# board1.net
KiCad netlist of a schematic drawn in EAGLE
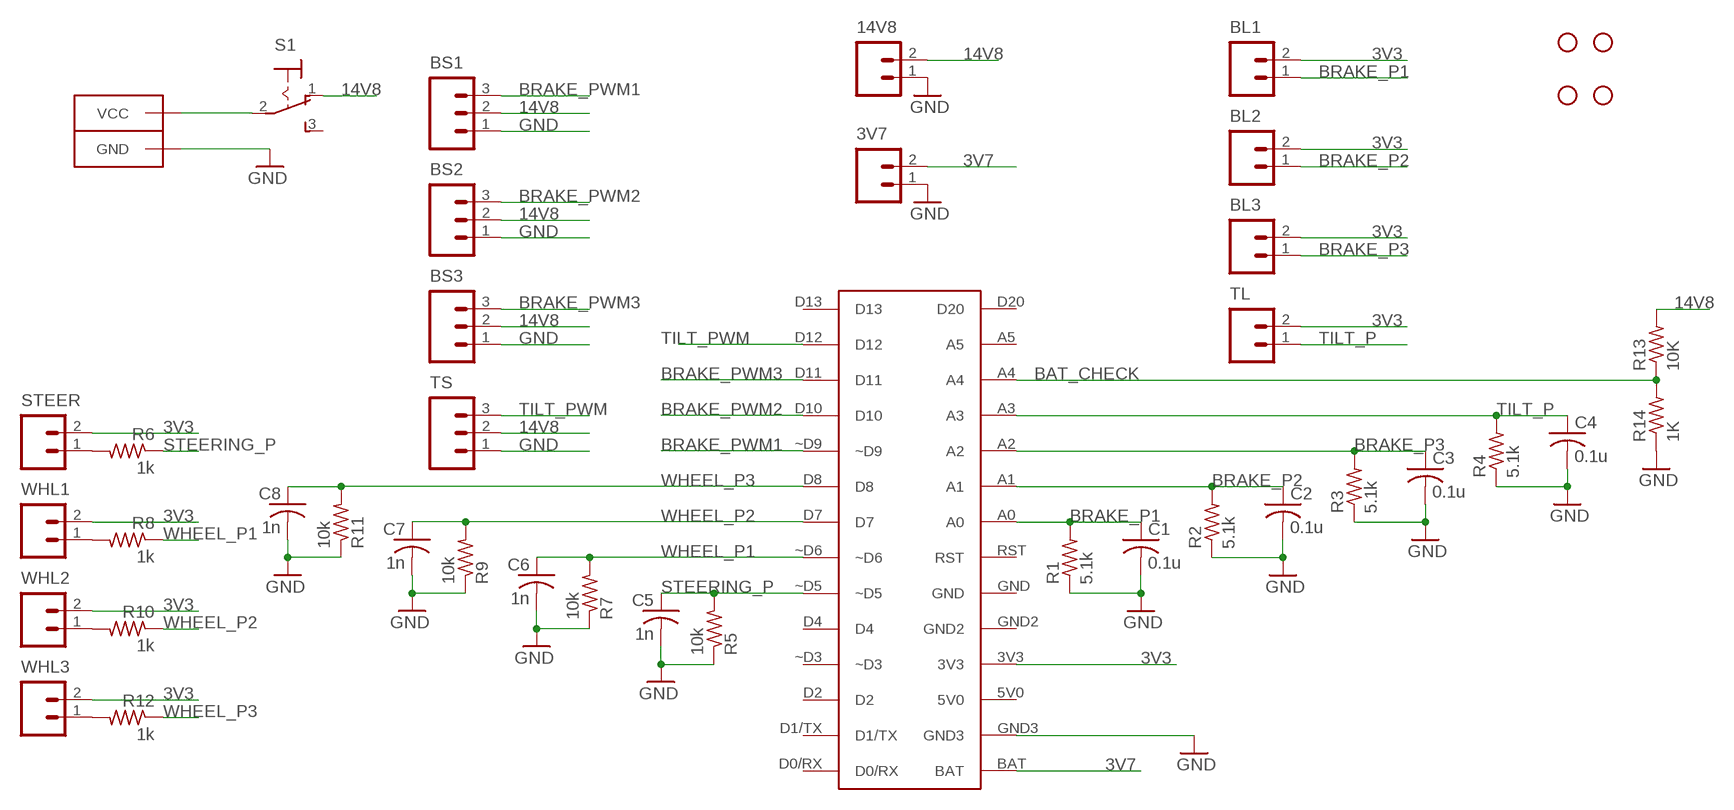
[diagram p0: schematic, sheet 1]

(export (version "E")
  (design (tool "Eeschema 10.0.6"))
  (components
    (comp (ref "3V7")
      (value "M02PTH")
      (footprint "eagle-import:1X02")
      (libsource (lib "eagle-import") (part "M02PTH"))
    )
    (comp (ref "14V8")
      (value "M02PTH")
      (footprint "eagle-import:1X02")
      (libsource (lib "eagle-import") (part "M02PTH"))
    )
    (comp (ref "BL1")
      (value "M02PTH")
      (footprint "eagle-import:1X02")
      (libsource (lib "eagle-import") (part "M02PTH"))
    )
    (comp (ref "BL2")
      (value "M02PTH")
      (footprint "eagle-import:1X02")
      (libsource (lib "eagle-import") (part "M02PTH"))
    )
    (comp (ref "BL3")
      (value "M02PTH")
      (footprint "eagle-import:1X02")
      (libsource (lib "eagle-import") (part "M02PTH"))
    )
    (comp (ref "BS1")
      (value "M03PTH")
      (footprint "eagle-import:1X03")
      (libsource (lib "eagle-import") (part "M03PTH"))
    )
    (comp (ref "BS2")
      (value "M03PTH")
      (footprint "eagle-import:1X03")
      (libsource (lib "eagle-import") (part "M03PTH"))
    )
    (comp (ref "BS3")
      (value "M03PTH")
      (footprint "eagle-import:1X03")
      (libsource (lib "eagle-import") (part "M03PTH"))
    )
    (comp (ref "C1")
      (value "0.1u")
      (footprint "eagle-import:C0603")
      (libsource (lib "eagle-import") (part "C-USC0603"))
    )
    (comp (ref "C2")
      (value "0.1u")
      (footprint "eagle-import:C0603")
      (libsource (lib "eagle-import") (part "C-USC0603"))
    )
    (comp (ref "C3")
      (value "0.1u")
      (footprint "eagle-import:C0603")
      (libsource (lib "eagle-import") (part "C-USC0603"))
    )
    (comp (ref "C4")
      (value "0.1u")
      (footprint "eagle-import:C0603")
      (libsource (lib "eagle-import") (part "C-USC0603"))
    )
    (comp (ref "C5")
      (value "1n")
      (footprint "eagle-import:C0603")
      (libsource (lib "eagle-import") (part "C-USC0603"))
    )
    (comp (ref "C6")
      (value "1n")
      (footprint "eagle-import:C0603")
      (libsource (lib "eagle-import") (part "C-USC0603"))
    )
    (comp (ref "C7")
      (value "1n")
      (footprint "eagle-import:C0603")
      (libsource (lib "eagle-import") (part "C-USC0603"))
    )
    (comp (ref "C8")
      (value "1n")
      (footprint "eagle-import:C0603")
      (libsource (lib "eagle-import") (part "C-USC0603"))
    )
    (comp (ref "JP13")
      (value "STAND-OFF")
      (footprint "eagle-import:STAND-OFF")
      (libsource (lib "eagle-import") (part "STAND-OFF"))
    )
    (comp (ref "JP14")
      (value "STAND-OFF")
      (footprint "eagle-import:STAND-OFF")
      (libsource (lib "eagle-import") (part "STAND-OFF"))
    )
    (comp (ref "JP15")
      (value "STAND-OFF")
      (footprint "eagle-import:STAND-OFF")
      (libsource (lib "eagle-import") (part "STAND-OFF"))
    )
    (comp (ref "JP16")
      (value "STAND-OFF")
      (footprint "eagle-import:STAND-OFF")
      (libsource (lib "eagle-import") (part "STAND-OFF"))
    )
    (comp (ref "LIPO")
      (value "ANDERSONHORIZONTAL")
      (footprint "eagle-import:ANDERSON_HORIZONTAL")
      (libsource (lib "eagle-import") (part "ANDERSONHORIZONTAL"))
    )
    (comp (ref "R1")
      (value "5.1k")
      (footprint "eagle-import:R0603")
      (libsource (lib "eagle-import") (part "R-US_R0603"))
    )
    (comp (ref "R2")
      (value "5.1k")
      (footprint "eagle-import:R0603")
      (libsource (lib "eagle-import") (part "R-US_R0603"))
    )
    (comp (ref "R3")
      (value "5.1k")
      (footprint "eagle-import:R0603")
      (libsource (lib "eagle-import") (part "R-US_R0603"))
    )
    (comp (ref "R4")
      (value "5.1k")
      (footprint "eagle-import:R0603")
      (libsource (lib "eagle-import") (part "R-US_R0603"))
    )
    (comp (ref "R5")
      (value "10k")
      (footprint "eagle-import:R0603")
      (libsource (lib "eagle-import") (part "R-US_R0603"))
    )
    (comp (ref "R6")
      (value "1k")
      (footprint "eagle-import:R0603")
      (libsource (lib "eagle-import") (part "R-US_R0603"))
    )
    (comp (ref "R7")
      (value "10k")
      (footprint "eagle-import:R0603")
      (libsource (lib "eagle-import") (part "R-US_R0603"))
    )
    (comp (ref "R8")
      (value "1k")
      (footprint "eagle-import:R0603")
      (libsource (lib "eagle-import") (part "R-US_R0603"))
    )
    (comp (ref "R9")
      (value "10k")
      (footprint "eagle-import:R0603")
      (libsource (lib "eagle-import") (part "R-US_R0603"))
    )
    (comp (ref "R10")
      (value "1k")
      (footprint "eagle-import:R0603")
      (libsource (lib "eagle-import") (part "R-US_R0603"))
    )
    (comp (ref "R11")
      (value "10k")
      (footprint "eagle-import:R0603")
      (libsource (lib "eagle-import") (part "R-US_R0603"))
    )
    (comp (ref "R12")
      (value "1k")
      (footprint "eagle-import:R0603")
      (libsource (lib "eagle-import") (part "R-US_R0603"))
    )
    (comp (ref "R13")
      (value "10K")
      (footprint "eagle-import:R0603")
      (libsource (lib "eagle-import") (part "R-US_R0603"))
    )
    (comp (ref "R14")
      (value "1K")
      (footprint "eagle-import:R0603")
      (libsource (lib "eagle-import") (part "R-US_R0603"))
    )
    (comp (ref "S1")
      (value "M9040P")
      (footprint "eagle-import:M9040P")
      (libsource (lib "eagle-import") (part "M9040P"))
    )
    (comp (ref "STEER")
      (value "M02PTH")
      (footprint "eagle-import:1X02")
      (libsource (lib "eagle-import") (part "M02PTH"))
    )
    (comp (ref "TL")
      (value "M02PTH")
      (footprint "eagle-import:1X02")
      (libsource (lib "eagle-import") (part "M02PTH"))
    )
    (comp (ref "TS")
      (value "M03PTH")
      (footprint "eagle-import:1X03")
      (libsource (lib "eagle-import") (part "M03PTH"))
    )
    (comp (ref "U$1")
      (value "CURIENANO_BREAKOUT")
      (footprint "eagle-import:CURIENANO")
      (libsource (lib "eagle-import") (part "CURIENANO_BREAKOUT"))
    )
    (comp (ref "WHL1")
      (value "M02PTH")
      (footprint "eagle-import:1X02")
      (libsource (lib "eagle-import") (part "M02PTH"))
    )
    (comp (ref "WHL2")
      (value "M02PTH")
      (footprint "eagle-import:1X02")
      (libsource (lib "eagle-import") (part "M02PTH"))
    )
    (comp (ref "WHL3")
      (value "M02PTH")
      (footprint "eagle-import:1X02")
      (libsource (lib "eagle-import") (part "M02PTH"))
    )
  )
  (nets
    (net (code "1") (name "/3V3") (class "Default")
      (node (ref "BL1") (pin "2") (pinfunction "2_2") (pintype "passive"))
      (node (ref "BL2") (pin "2") (pinfunction "2_2") (pintype "passive"))
      (node (ref "BL3") (pin "2") (pinfunction "2_2") (pintype "passive"))
      (node (ref "STEER") (pin "2") (pinfunction "2_2") (pintype "passive"))
      (node (ref "TL") (pin "2") (pinfunction "2_2") (pintype "passive"))
      (node (ref "U$1") (pin "3V3") (pinfunction "3V3_3V3") (pintype "bidirectional"))
      (node (ref "WHL1") (pin "2") (pinfunction "2_2") (pintype "passive"))
      (node (ref "WHL2") (pin "2") (pinfunction "2_2") (pintype "passive"))
      (node (ref "WHL3") (pin "2") (pinfunction "2_2") (pintype "passive"))
    )
    (net (code "2") (name "/3V7") (class "Default")
      (node (ref "3V7") (pin "2") (pinfunction "2_2") (pintype "passive"))
      (node (ref "U$1") (pin "BAT") (pinfunction "BAT_BAT") (pintype "bidirectional"))
    )
    (net (code "3") (name "/14V8") (class "Default")
      (node (ref "14V8") (pin "2") (pinfunction "2_2") (pintype "passive"))
      (node (ref "BS1") (pin "2") (pinfunction "2_2") (pintype "passive"))
      (node (ref "BS2") (pin "2") (pinfunction "2_2") (pintype "passive"))
      (node (ref "BS3") (pin "2") (pinfunction "2_2") (pintype "passive"))
      (node (ref "R13") (pin "2") (pinfunction "2_2") (pintype "passive"))
      (node (ref "S1") (pin "1") (pinfunction "O_1") (pintype "passive"))
      (node (ref "TS") (pin "2") (pinfunction "2_2") (pintype "passive"))
    )
    (net (code "4") (name "/BAT_CHECK") (class "Default")
      (node (ref "R13") (pin "1") (pinfunction "1_1") (pintype "passive"))
      (node (ref "R14") (pin "2") (pinfunction "2_2") (pintype "passive"))
      (node (ref "U$1") (pin "A4") (pinfunction "A4_A4") (pintype "bidirectional"))
    )
    (net (code "5") (name "/BRAKE_P1") (class "Default")
      (node (ref "BL1") (pin "1") (pinfunction "1_1") (pintype "passive"))
      (node (ref "C1") (pin "1") (pinfunction "1_1") (pintype "passive"))
      (node (ref "R1") (pin "2") (pinfunction "2_2") (pintype "passive"))
      (node (ref "U$1") (pin "A0") (pinfunction "A0_A0") (pintype "bidirectional"))
    )
    (net (code "6") (name "/BRAKE_P2") (class "Default")
      (node (ref "BL2") (pin "1") (pinfunction "1_1") (pintype "passive"))
      (node (ref "C2") (pin "1") (pinfunction "1_1") (pintype "passive"))
      (node (ref "R2") (pin "2") (pinfunction "2_2") (pintype "passive"))
      (node (ref "U$1") (pin "A1") (pinfunction "A1_A1") (pintype "bidirectional"))
    )
    (net (code "7") (name "/BRAKE_P3") (class "Default")
      (node (ref "BL3") (pin "1") (pinfunction "1_1") (pintype "passive"))
      (node (ref "C3") (pin "1") (pinfunction "1_1") (pintype "passive"))
      (node (ref "R3") (pin "2") (pinfunction "2_2") (pintype "passive"))
      (node (ref "U$1") (pin "A2") (pinfunction "A2_A2") (pintype "bidirectional"))
    )
    (net (code "8") (name "/BRAKE_PWM1") (class "Default")
      (node (ref "BS1") (pin "3") (pinfunction "3_3") (pintype "passive"))
      (node (ref "U$1") (pin "~D9") (pinfunction "~{D9}_~D9") (pintype "bidirectional"))
    )
    (net (code "9") (name "/BRAKE_PWM2") (class "Default")
      (node (ref "BS2") (pin "3") (pinfunction "3_3") (pintype "passive"))
      (node (ref "U$1") (pin "D10") (pinfunction "D10_D10") (pintype "bidirectional"))
    )
    (net (code "10") (name "/BRAKE_PWM3") (class "Default")
      (node (ref "BS3") (pin "3") (pinfunction "3_3") (pintype "passive"))
      (node (ref "U$1") (pin "D11") (pinfunction "D11_D11") (pintype "bidirectional"))
    )
    (net (code "11") (name "/STEERING_P") (class "Default")
      (node (ref "C5") (pin "1") (pinfunction "1_1") (pintype "passive"))
      (node (ref "R5") (pin "2") (pinfunction "2_2") (pintype "passive"))
      (node (ref "R6") (pin "1") (pinfunction "1_1") (pintype "passive"))
      (node (ref "U$1") (pin "~D5") (pinfunction "~{D5}_~D5") (pintype "bidirectional"))
    )
    (net (code "12") (name "/TILT_P") (class "Default")
      (node (ref "C4") (pin "1") (pinfunction "1_1") (pintype "passive"))
      (node (ref "R4") (pin "2") (pinfunction "2_2") (pintype "passive"))
      (node (ref "TL") (pin "1") (pinfunction "1_1") (pintype "passive"))
      (node (ref "U$1") (pin "A3") (pinfunction "A3_A3") (pintype "bidirectional"))
    )
    (net (code "13") (name "/TILT_PWM") (class "Default")
      (node (ref "TS") (pin "3") (pinfunction "3_3") (pintype "passive"))
      (node (ref "U$1") (pin "D12") (pinfunction "D12_D12") (pintype "bidirectional"))
    )
    (net (code "14") (name "/WHEEL_P1") (class "Default")
      (node (ref "C6") (pin "1") (pinfunction "1_1") (pintype "passive"))
      (node (ref "R7") (pin "2") (pinfunction "2_2") (pintype "passive"))
      (node (ref "R8") (pin "1") (pinfunction "1_1") (pintype "passive"))
      (node (ref "U$1") (pin "~D6") (pinfunction "~{D6}_~D6") (pintype "bidirectional"))
    )
    (net (code "15") (name "/WHEEL_P2") (class "Default")
      (node (ref "C7") (pin "1") (pinfunction "1_1") (pintype "passive"))
      (node (ref "R10") (pin "1") (pinfunction "1_1") (pintype "passive"))
      (node (ref "R9") (pin "2") (pinfunction "2_2") (pintype "passive"))
      (node (ref "U$1") (pin "D7") (pinfunction "D7_D7") (pintype "bidirectional"))
    )
    (net (code "16") (name "/WHEEL_P3") (class "Default")
      (node (ref "C8") (pin "1") (pinfunction "1_1") (pintype "passive"))
      (node (ref "R11") (pin "2") (pinfunction "2_2") (pintype "passive"))
      (node (ref "R12") (pin "1") (pinfunction "1_1") (pintype "passive"))
      (node (ref "U$1") (pin "D8") (pinfunction "D8_D8") (pintype "bidirectional"))
    )
    (net (code "17") (name "GND") (class "Default")
      (node (ref "14V8") (pin "1") (pinfunction "1_1") (pintype "passive"))
      (node (ref "3V7") (pin "1") (pinfunction "1_1") (pintype "passive"))
      (node (ref "BS1") (pin "1") (pinfunction "1_1") (pintype "passive"))
      (node (ref "BS2") (pin "1") (pinfunction "1_1") (pintype "passive"))
      (node (ref "BS3") (pin "1") (pinfunction "1_1") (pintype "passive"))
      (node (ref "C1") (pin "2") (pinfunction "2_2") (pintype "passive"))
      (node (ref "C2") (pin "2") (pinfunction "2_2") (pintype "passive"))
      (node (ref "C3") (pin "2") (pinfunction "2_2") (pintype "passive"))
      (node (ref "C4") (pin "2") (pinfunction "2_2") (pintype "passive"))
      (node (ref "C5") (pin "2") (pinfunction "2_2") (pintype "passive"))
      (node (ref "C6") (pin "2") (pinfunction "2_2") (pintype "passive"))
      (node (ref "C7") (pin "2") (pinfunction "2_2") (pintype "passive"))
      (node (ref "C8") (pin "2") (pinfunction "2_2") (pintype "passive"))
      (node (ref "LIPO") (pin "PIN1") (pinfunction "GND_PIN1") (pintype "bidirectional"))
      (node (ref "LIPO") (pin "PIN1-LEAD") (pinfunction "GND_PIN1-LEAD") (pintype "bidirectional"))
      (node (ref "R1") (pin "1") (pinfunction "1_1") (pintype "passive"))
      (node (ref "R11") (pin "1") (pinfunction "1_1") (pintype "passive"))
      (node (ref "R14") (pin "1") (pinfunction "1_1") (pintype "passive"))
      (node (ref "R2") (pin "1") (pinfunction "1_1") (pintype "passive"))
      (node (ref "R3") (pin "1") (pinfunction "1_1") (pintype "passive"))
      (node (ref "R4") (pin "1") (pinfunction "1_1") (pintype "passive"))
      (node (ref "R5") (pin "1") (pinfunction "1_1") (pintype "passive"))
      (node (ref "R7") (pin "1") (pinfunction "1_1") (pintype "passive"))
      (node (ref "R9") (pin "1") (pinfunction "1_1") (pintype "passive"))
      (node (ref "TS") (pin "1") (pinfunction "1_1") (pintype "passive"))
      (node (ref "U$1") (pin "GND3") (pinfunction "GND3_GND3") (pintype "bidirectional"))
    )
    (net (code "18") (name "Net-(R6-Pad2)") (class "Default")
      (node (ref "R6") (pin "2") (pinfunction "2_2") (pintype "passive"))
      (node (ref "STEER") (pin "1") (pinfunction "1_1") (pintype "passive"))
    )
    (net (code "19") (name "Net-(R8-Pad2)") (class "Default")
      (node (ref "R8") (pin "2") (pinfunction "2_2") (pintype "passive"))
      (node (ref "WHL1") (pin "1") (pinfunction "1_1") (pintype "passive"))
    )
    (net (code "20") (name "Net-(R10-Pad2)") (class "Default")
      (node (ref "R10") (pin "2") (pinfunction "2_2") (pintype "passive"))
      (node (ref "WHL2") (pin "1") (pinfunction "1_1") (pintype "passive"))
    )
    (net (code "21") (name "Net-(R12-Pad2)") (class "Default")
      (node (ref "R12") (pin "2") (pinfunction "2_2") (pintype "passive"))
      (node (ref "WHL3") (pin "1") (pinfunction "1_1") (pintype "passive"))
    )
    (net (code "22") (name "Net-(S1-P)") (class "Default")
      (node (ref "LIPO") (pin "PIN2") (pinfunction "VCC_PIN2") (pintype "bidirectional"))
      (node (ref "LIPO") (pin "PIN2-LEAD") (pinfunction "VCC_PIN2-LEAD") (pintype "bidirectional"))
      (node (ref "S1") (pin "2") (pinfunction "P_2") (pintype "passive"))
    )
    (net (code "23") (name "unconnected-(S1-S-Pad3)") (class "Default")
      (node (ref "S1") (pin "3") (pinfunction "S_3") (pintype "passive"))
    )
    (net (code "24") (name "unconnected-(U$1-Pad5V0)") (class "Default")
      (node (ref "U$1") (pin "5V0") (pinfunction "5V0_5V0") (pintype "bidirectional"))
    )
    (net (code "25") (name "unconnected-(U$1-PadA5)") (class "Default")
      (node (ref "U$1") (pin "A5") (pinfunction "A5_A5") (pintype "bidirectional"))
    )
    (net (code "26") (name "unconnected-(U$1-PadD0{slash}RX)") (class "Default")
      (node (ref "U$1") (pin "D0/RX") (pinfunction "D0/RX_D0/RX") (pintype "bidirectional"))
    )
    (net (code "27") (name "unconnected-(U$1-PadD1{slash}TX)") (class "Default")
      (node (ref "U$1") (pin "D1/TX") (pinfunction "D1/TX_D1/TX") (pintype "bidirectional"))
    )
    (net (code "28") (name "unconnected-(U$1-PadD2)") (class "Default")
      (node (ref "U$1") (pin "D2") (pinfunction "D2_D2") (pintype "bidirectional"))
    )
    (net (code "29") (name "unconnected-(U$1-PadD4)") (class "Default")
      (node (ref "U$1") (pin "D4") (pinfunction "D4_D4") (pintype "bidirectional"))
    )
    (net (code "30") (name "unconnected-(U$1-PadD13)") (class "Default")
      (node (ref "U$1") (pin "D13") (pinfunction "D13_D13") (pintype "bidirectional"))
    )
    (net (code "31") (name "unconnected-(U$1-PadD20)") (class "Default")
      (node (ref "U$1") (pin "D20") (pinfunction "D20_D20") (pintype "bidirectional"))
    )
    (net (code "32") (name "unconnected-(U$1-PadGND)") (class "Default")
      (node (ref "U$1") (pin "GND") (pinfunction "GND_GND") (pintype "bidirectional"))
    )
    (net (code "33") (name "unconnected-(U$1-PadGND2)") (class "Default")
      (node (ref "U$1") (pin "GND2") (pinfunction "GND2_GND2") (pintype "bidirectional"))
    )
    (net (code "34") (name "unconnected-(U$1-PadRST)") (class "Default")
      (node (ref "U$1") (pin "RST") (pinfunction "RST_RST") (pintype "bidirectional"))
    )
    (net (code "35") (name "unconnected-(U$1-~{D3}-Pad~D3)") (class "Default")
      (node (ref "U$1") (pin "~D3") (pinfunction "~{D3}_~D3") (pintype "bidirectional"))
    )
  )
)
